# sch.net
KiCad netlist of a schematic drawn in EasyEDA
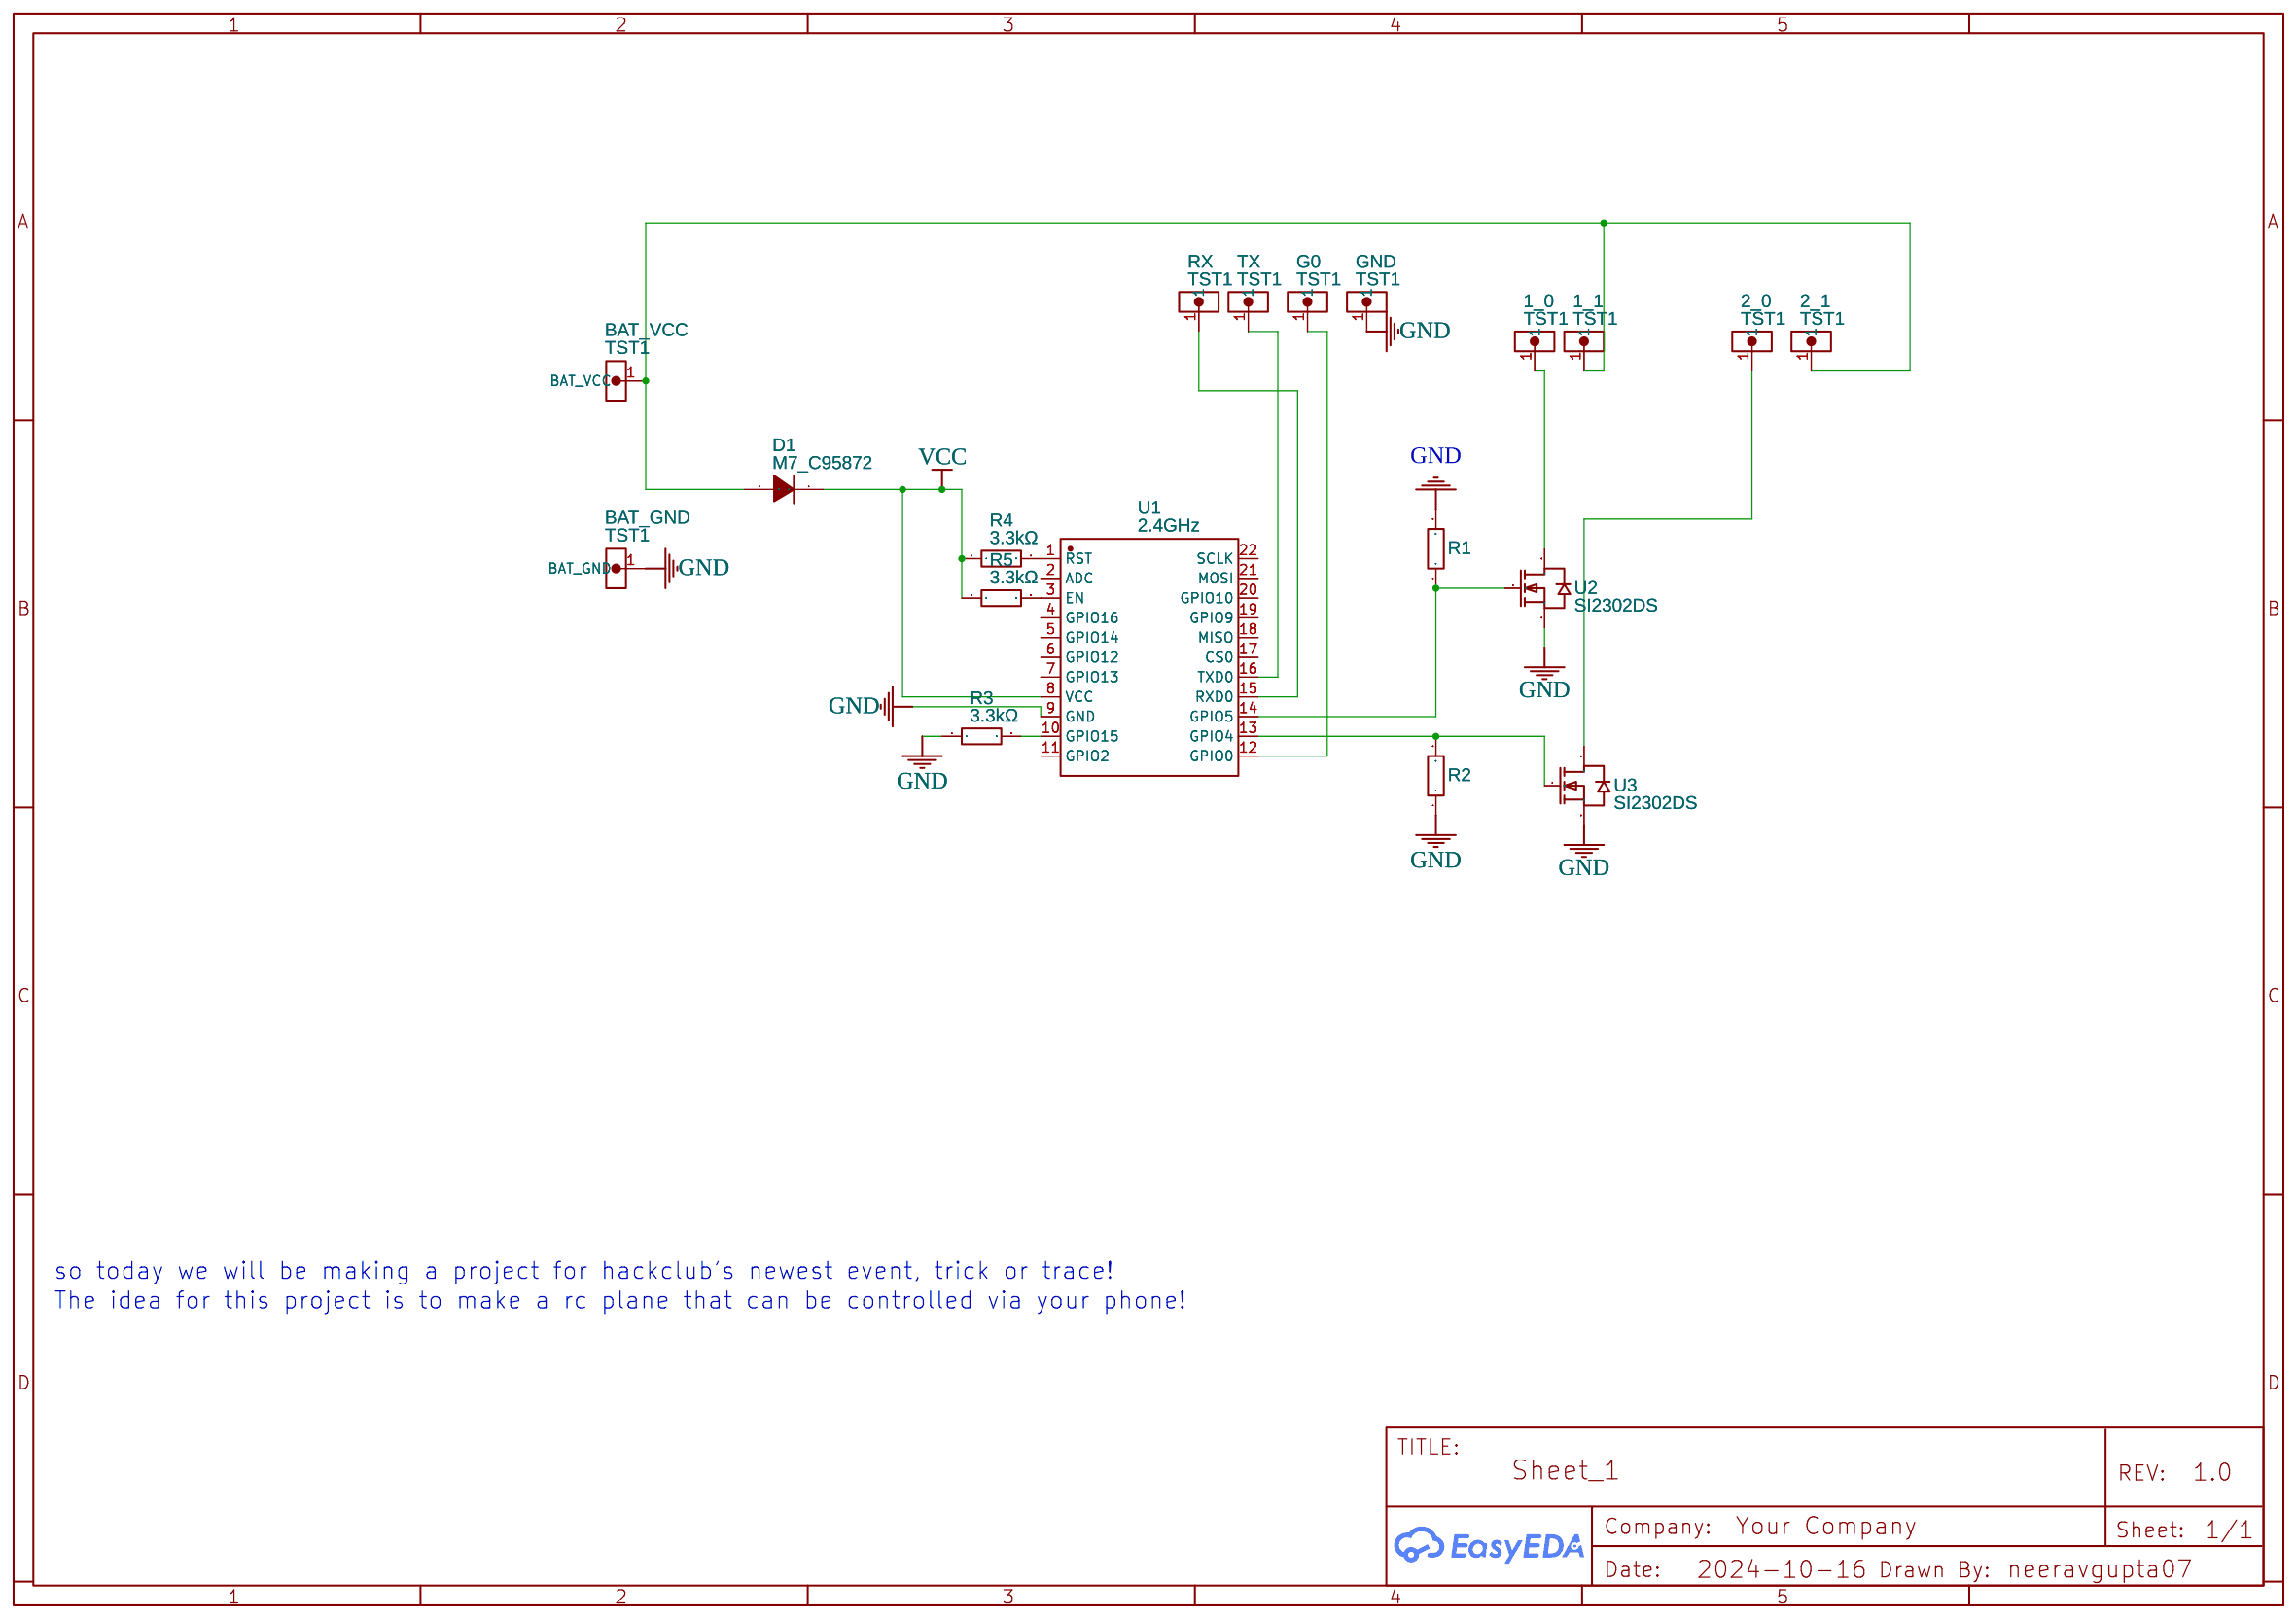
[diagram p0: schematic sheet]

(export (version "E")
  (design (tool "Eeschema 10.0.6"))
  (components
    (comp (ref "1_0")
      (value "TST1")
      (fields (field (name "Manufacturer Part") "New SchematicLib"))
      (libsource (lib "") (part "1PIN_CONNECTOR PIN1 0X,0Y_5"))
    )
    (comp (ref "1_1")
      (value "TST1")
      (fields (field (name "Manufacturer Part") "New SchematicLib"))
      (libsource (lib "") (part "1PIN_CONNECTOR PIN1 0X,0Y_5"))
    )
    (comp (ref "2_0")
      (value "TST1")
      (fields (field (name "Manufacturer Part") "New SchematicLib"))
      (libsource (lib "") (part "1PIN_CONNECTOR PIN1 0X,0Y_6"))
    )
    (comp (ref "2_1")
      (value "TST1")
      (fields (field (name "Manufacturer Part") "New SchematicLib"))
      (libsource (lib "") (part "1PIN_CONNECTOR PIN1 0X,0Y_6"))
    )
    (comp (ref "BAT_GND")
      (value "TST1")
      (fields (field (name "Manufacturer Part") "New SchematicLib"))
      (libsource (lib "") (part "1PIN_CONNECTOR PIN1 0X,0Y_4"))
    )
    (comp (ref "BAT_VCC")
      (value "TST1")
      (fields (field (name "Manufacturer Part") "New SchematicLib"))
      (libsource (lib "") (part "1PIN_CONNECTOR PIN1 0X,0Y_7"))
    )
    (comp (ref "D1")
      (value "M7_C95872")
      (fields (field (name "Manufacturer Part") "M7") (field (name "Manufacturer") "MDD(辰达半导体)"))
      (libsource (lib "") (part "M7_C95872"))
    )
    (comp (ref "G0")
      (value "TST1")
      (fields (field (name "Manufacturer Part") "New SchematicLib"))
      (libsource (lib "") (part "1PIN_CONNECTOR PIN1 0X,0Y_2"))
    )
    (comp (ref "GND")
      (value "TST1")
      (fields (field (name "Manufacturer Part") "New SchematicLib"))
      (libsource (lib "") (part "1PIN_CONNECTOR PIN1 0X,0Y"))
    )
    (comp (ref "R1")
      (value "3.3kΩ")
      (fields
        (field (name "Manufacturer Part") "0805W8F3301T5E")
        (field (name "Manufacturer") "UNI-ROYAL(厚声)")
      )
      (libsource (lib "") (part "0805W8F3301T5E"))
    )
    (comp (ref "R2")
      (value "3.3kΩ")
      (fields
        (field (name "Manufacturer Part") "0805W8F3301T5E")
        (field (name "Manufacturer") "UNI-ROYAL(厚声)")
      )
      (libsource (lib "") (part "0805W8F3301T5E"))
    )
    (comp (ref "R3")
      (value "3.3kΩ")
      (fields
        (field (name "Manufacturer Part") "0805W8F3301T5E")
        (field (name "Manufacturer") "UNI-ROYAL(厚声)")
      )
      (libsource (lib "") (part "0805W8F3301T5E_1"))
    )
    (comp (ref "R4")
      (value "3.3kΩ")
      (fields
        (field (name "Manufacturer Part") "0805W8F3301T5E")
        (field (name "Manufacturer") "UNI-ROYAL(厚声)")
      )
      (libsource (lib "") (part "0805W8F3301T5E_1"))
    )
    (comp (ref "R5")
      (value "3.3kΩ")
      (fields
        (field (name "Manufacturer Part") "0805W8F3301T5E")
        (field (name "Manufacturer") "UNI-ROYAL(厚声)")
      )
      (libsource (lib "") (part "0805W8F3301T5E_1"))
    )
    (comp (ref "RX")
      (value "TST1")
      (fields (field (name "Manufacturer Part") "New SchematicLib"))
      (libsource (lib "") (part "1PIN_CONNECTOR PIN1 0X,0Y_1"))
    )
    (comp (ref "TX")
      (value "TST1")
      (fields (field (name "Manufacturer Part") "New SchematicLib"))
      (libsource (lib "") (part "1PIN_CONNECTOR PIN1 0X,0Y_3"))
    )
    (comp (ref "U1")
      (value "2.4GHz")
      (fields
        (field (name "Manufacturer Part") "ESP-12F(ESP8266MOD)")
        (field (name "Manufacturer") "Ai-Thinker(安信可)")
      )
      (libsource (lib "") (part "ESP-12F(ESP8266MOD)"))
    )
    (comp (ref "U2")
      (value "SI2302DS")
      (fields (field (name "Manufacturer") "TECH PUBLIC(台舟)"))
      (libsource (lib "") (part "SI2302DS"))
    )
    (comp (ref "U3")
      (value "SI2302DS")
      (fields (field (name "Manufacturer") "TECH PUBLIC(台舟)"))
      (libsource (lib "") (part "SI2302DS"))
    )
  )
  (nets
    (net (code "1") (name "GND") (class "Default")
      (node (ref "BAT_GND") (pin "1") (pinfunction "BAT_GND_1") (pintype "unspecified"))
      (node (ref "GND") (pin "1") (pinfunction "1_1") (pintype "unspecified"))
      (node (ref "R1") (pin "2") (pinfunction "2_2") (pintype "input"))
      (node (ref "R2") (pin "1") (pinfunction "1_1") (pintype "input"))
      (node (ref "R3") (pin "1") (pinfunction "1_1") (pintype "input"))
      (node (ref "U1") (pin "9") (pinfunction "GND_9") (pintype "unspecified"))
      (node (ref "U2") (pin "2") (pinfunction "S_2") (pintype "unspecified"))
      (node (ref "U3") (pin "2") (pinfunction "S_2") (pintype "unspecified"))
    )
    (net (code "2") (name "Net-(BAT_VCC-BAT_VCC)") (class "Default")
      (node (ref "1_1") (pin "1") (pinfunction "1_1") (pintype "unspecified"))
      (node (ref "2_1") (pin "1") (pinfunction "1_1") (pintype "unspecified"))
      (node (ref "BAT_VCC") (pin "1") (pinfunction "BAT_VCC_1") (pintype "unspecified"))
      (node (ref "D1") (pin "2") (pinfunction "A_2") (pintype "unspecified"))
    )
    (net (code "3") (name "Net-(U1-EN)") (class "Default")
      (node (ref "R5") (pin "2") (pinfunction "2_2") (pintype "input"))
      (node (ref "U1") (pin "3") (pinfunction "EN_3") (pintype "unspecified"))
    )
    (net (code "4") (name "Net-(U1-GPIO0)") (class "Default")
      (node (ref "G0") (pin "1") (pinfunction "1_1") (pintype "unspecified"))
      (node (ref "U1") (pin "12") (pinfunction "GPIO0_12") (pintype "unspecified"))
    )
    (net (code "5") (name "Net-(U1-GPIO4)") (class "Default")
      (node (ref "R2") (pin "2") (pinfunction "2_2") (pintype "input"))
      (node (ref "U1") (pin "13") (pinfunction "GPIO4_13") (pintype "unspecified"))
      (node (ref "U3") (pin "1") (pinfunction "G_1") (pintype "unspecified"))
    )
    (net (code "6") (name "Net-(U1-GPIO5)") (class "Default")
      (node (ref "R1") (pin "1") (pinfunction "1_1") (pintype "input"))
      (node (ref "U1") (pin "14") (pinfunction "GPIO5_14") (pintype "unspecified"))
      (node (ref "U2") (pin "1") (pinfunction "G_1") (pintype "unspecified"))
    )
    (net (code "7") (name "Net-(U1-GPIO15)") (class "Default")
      (node (ref "R3") (pin "2") (pinfunction "2_2") (pintype "input"))
      (node (ref "U1") (pin "10") (pinfunction "GPIO15_10") (pintype "unspecified"))
    )
    (net (code "8") (name "Net-(U1-RST)") (class "Default")
      (node (ref "R4") (pin "2") (pinfunction "2_2") (pintype "input"))
      (node (ref "U1") (pin "1") (pinfunction "RST_1") (pintype "unspecified"))
    )
    (net (code "9") (name "Net-(U1-RXD0)") (class "Default")
      (node (ref "RX") (pin "1") (pinfunction "1_1") (pintype "unspecified"))
      (node (ref "U1") (pin "15") (pinfunction "RXD0_15") (pintype "unspecified"))
    )
    (net (code "10") (name "Net-(U1-TXD0)") (class "Default")
      (node (ref "TX") (pin "1") (pinfunction "1_1") (pintype "unspecified"))
      (node (ref "U1") (pin "16") (pinfunction "TXD0_16") (pintype "unspecified"))
    )
    (net (code "11") (name "Net-(U2-D)") (class "Default")
      (node (ref "1_0") (pin "1") (pinfunction "1_1") (pintype "unspecified"))
      (node (ref "U2") (pin "3") (pinfunction "D_3") (pintype "unspecified"))
    )
    (net (code "12") (name "Net-(U3-D)") (class "Default")
      (node (ref "2_0") (pin "1") (pinfunction "1_1") (pintype "unspecified"))
      (node (ref "U3") (pin "3") (pinfunction "D_3") (pintype "unspecified"))
    )
    (net (code "13") (name "VCC") (class "Default")
      (node (ref "D1") (pin "1") (pinfunction "K_1") (pintype "unspecified"))
      (node (ref "R4") (pin "1") (pinfunction "1_1") (pintype "input"))
      (node (ref "R5") (pin "1") (pinfunction "1_1") (pintype "input"))
      (node (ref "U1") (pin "8") (pinfunction "VCC_8") (pintype "unspecified"))
    )
    (net (code "14") (name "unconnected-(U1-ADC-Pad2)") (class "Default")
      (node (ref "U1") (pin "2") (pinfunction "ADC_2") (pintype "unspecified"))
    )
    (net (code "15") (name "unconnected-(U1-CS0-Pad17)") (class "Default")
      (node (ref "U1") (pin "17") (pinfunction "CS0_17") (pintype "unspecified"))
    )
    (net (code "16") (name "unconnected-(U1-GPIO2-Pad11)") (class "Default")
      (node (ref "U1") (pin "11") (pinfunction "GPIO2_11") (pintype "unspecified"))
    )
    (net (code "17") (name "unconnected-(U1-GPIO9-Pad19)") (class "Default")
      (node (ref "U1") (pin "19") (pinfunction "GPIO9_19") (pintype "unspecified"))
    )
    (net (code "18") (name "unconnected-(U1-GPIO10-Pad20)") (class "Default")
      (node (ref "U1") (pin "20") (pinfunction "GPIO10_20") (pintype "unspecified"))
    )
    (net (code "19") (name "unconnected-(U1-GPIO12-Pad6)") (class "Default")
      (node (ref "U1") (pin "6") (pinfunction "GPIO12_6") (pintype "unspecified"))
    )
    (net (code "20") (name "unconnected-(U1-GPIO13-Pad7)") (class "Default")
      (node (ref "U1") (pin "7") (pinfunction "GPIO13_7") (pintype "unspecified"))
    )
    (net (code "21") (name "unconnected-(U1-GPIO14-Pad5)") (class "Default")
      (node (ref "U1") (pin "5") (pinfunction "GPIO14_5") (pintype "unspecified"))
    )
    (net (code "22") (name "unconnected-(U1-GPIO16-Pad4)") (class "Default")
      (node (ref "U1") (pin "4") (pinfunction "GPIO16_4") (pintype "unspecified"))
    )
    (net (code "23") (name "unconnected-(U1-MISO-Pad18)") (class "Default")
      (node (ref "U1") (pin "18") (pinfunction "MISO_18") (pintype "unspecified"))
    )
    (net (code "24") (name "unconnected-(U1-MOSI-Pad21)") (class "Default")
      (node (ref "U1") (pin "21") (pinfunction "MOSI_21") (pintype "unspecified"))
    )
    (net (code "25") (name "unconnected-(U1-SCLK-Pad22)") (class "Default")
      (node (ref "U1") (pin "22") (pinfunction "SCLK_22") (pintype "unspecified"))
    )
  )
)
